# E-Reader.net
KiCad netlist of a schematic drawn in EAGLE
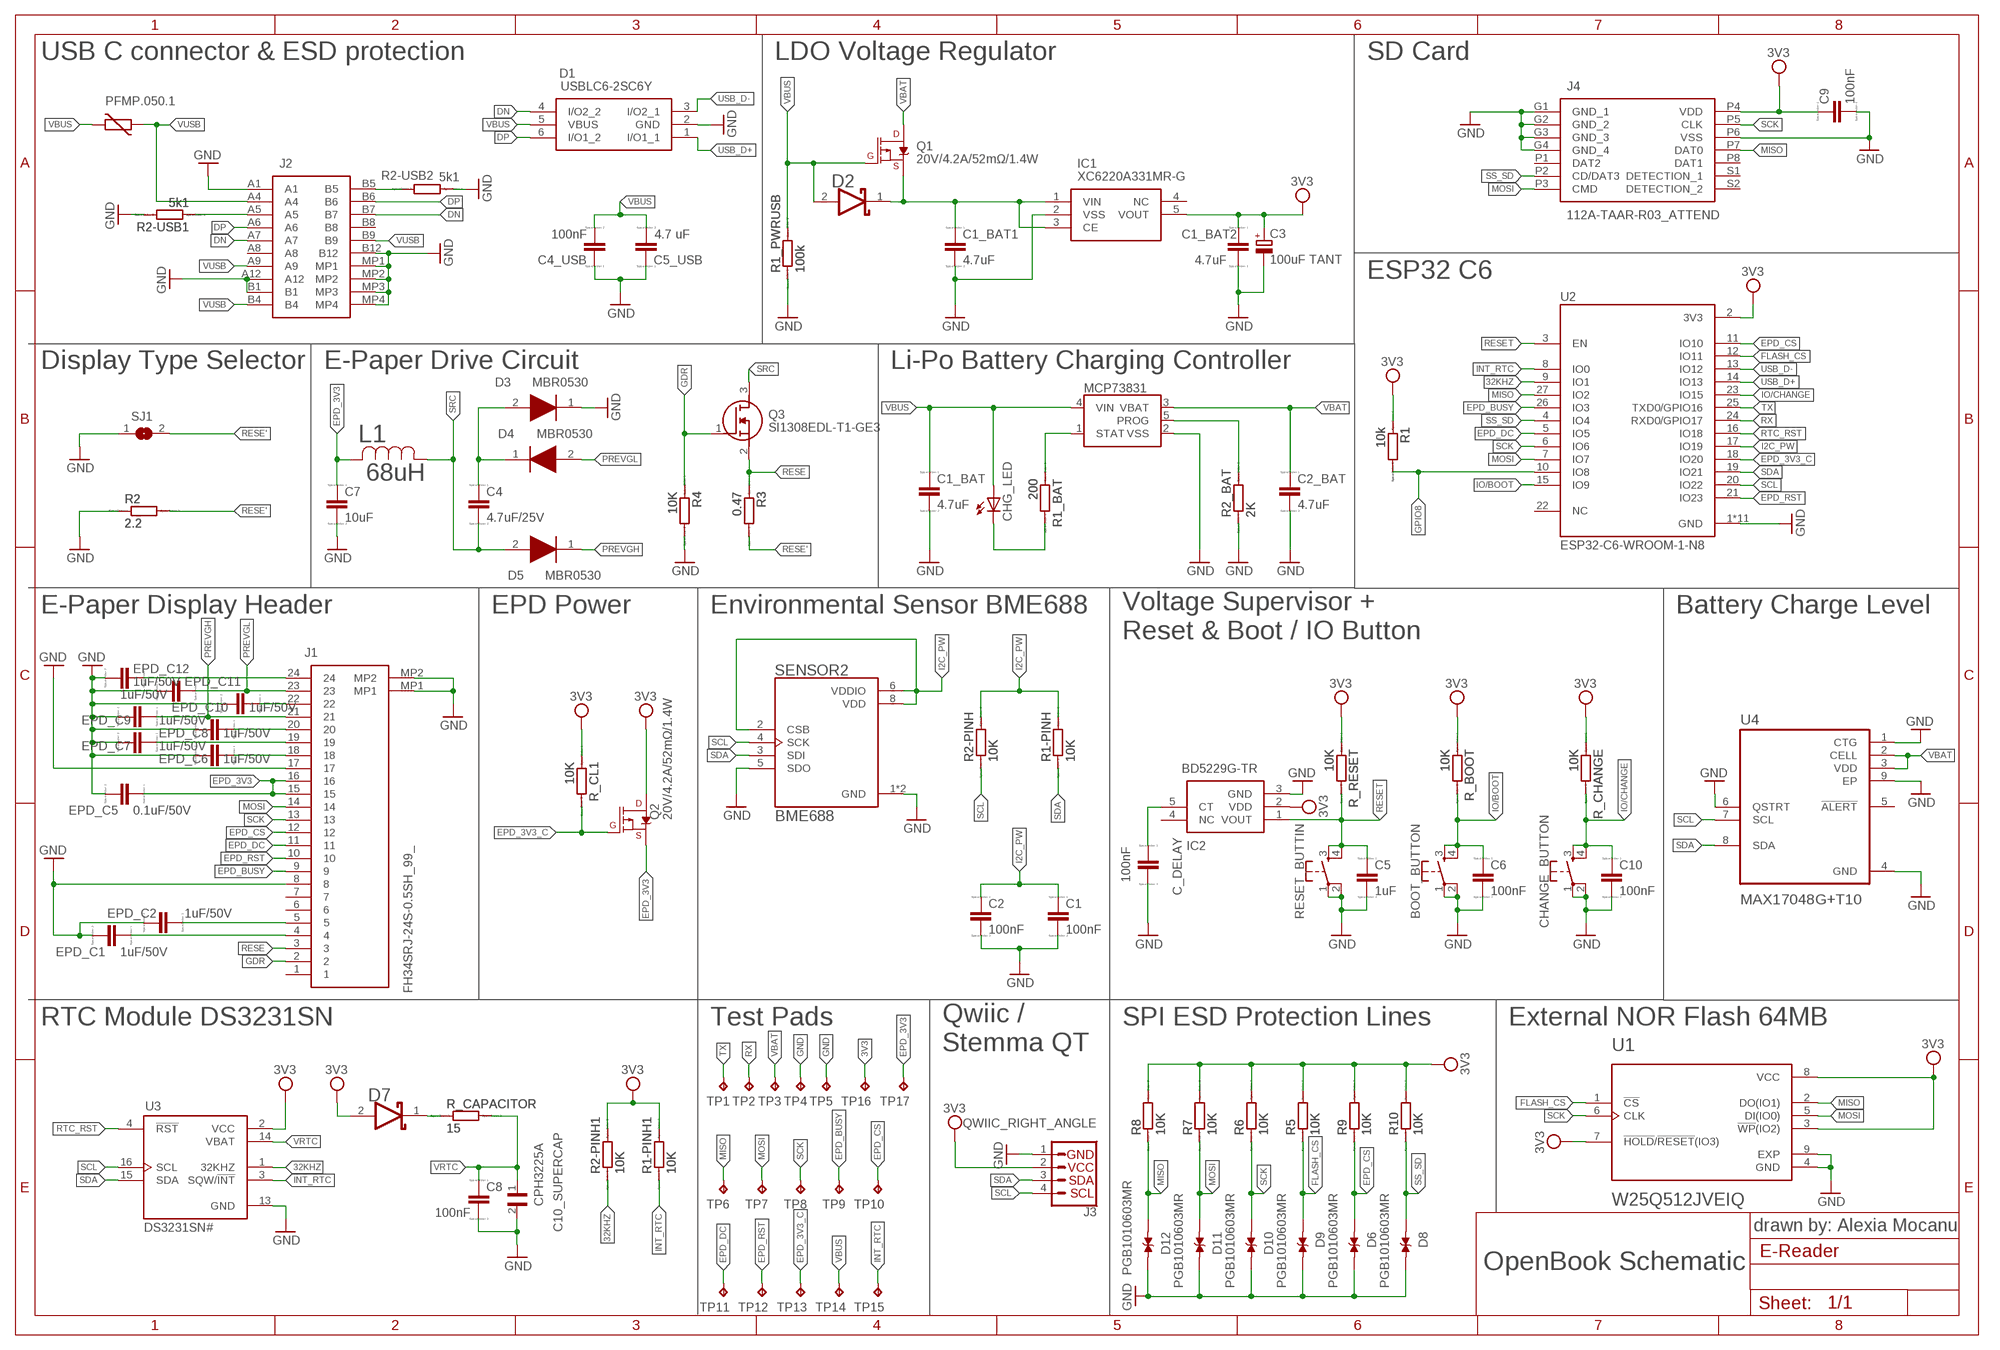
[diagram p0: schematic, sheet 1]

(export (version "E")
  (design (tool "Eeschema 10.0.6"))
  (components
    (comp (ref "BOOT_BUTTON")
      (value "BUTTON_CUSYOMV1")
      (footprint "eagle-import:MYBUTTON")
      (libsource (lib "eagle-import") (part "BUTTON_CUSYOMV1"))
    )
    (comp (ref "C1")
      (value "100nF")
      (footprint "eagle-import:EAGLE-LTSPICE_C0402")
      (libsource (lib "eagle-import") (part "EAGLE-LTSPICE_CC0402"))
    )
    (comp (ref "C1_BAT")
      (value "4.7uF")
      (footprint "eagle-import:EAGLE-LTSPICE_C0402")
      (libsource (lib "eagle-import") (part "EAGLE-LTSPICE_CC0402"))
    )
    (comp (ref "C1_BAT1")
      (value "4.7uF")
      (footprint "eagle-import:EAGLE-LTSPICE_C0402")
      (libsource (lib "eagle-import") (part "EAGLE-LTSPICE_CC0402"))
    )
    (comp (ref "C1_BAT2")
      (value "4.7uF")
      (footprint "eagle-import:EAGLE-LTSPICE_C0402")
      (libsource (lib "eagle-import") (part "EAGLE-LTSPICE_CC0402"))
    )
    (comp (ref "C2")
      (value "100nF")
      (footprint "eagle-import:EAGLE-LTSPICE_C0402")
      (libsource (lib "eagle-import") (part "EAGLE-LTSPICE_CC0402"))
    )
    (comp (ref "C2_BAT")
      (value "4.7uF")
      (footprint "eagle-import:EAGLE-LTSPICE_C0402")
      (libsource (lib "eagle-import") (part "EAGLE-LTSPICE_CC0402"))
    )
    (comp (ref "C3")
      (value "100uF TANT")
      (footprint "eagle-import:RCL_CT3528")
      (libsource (lib "eagle-import") (part "RCL_CPOL-EUCT3528"))
    )
    (comp (ref "C4")
      (value "4.7uF/25V")
      (footprint "eagle-import:EAGLE-LTSPICE_C0402")
      (libsource (lib "eagle-import") (part "EAGLE-LTSPICE_CC0402"))
    )
    (comp (ref "C4_USB")
      (value "100nF")
      (footprint "eagle-import:EAGLE-LTSPICE_C0402")
      (libsource (lib "eagle-import") (part "EAGLE-LTSPICE_CC0402"))
    )
    (comp (ref "C5")
      (value "1uF")
      (footprint "eagle-import:EAGLE-LTSPICE_C0402")
      (libsource (lib "eagle-import") (part "EAGLE-LTSPICE_CC0402"))
    )
    (comp (ref "C5_USB")
      (value "4.7 uF")
      (footprint "eagle-import:EAGLE-LTSPICE_C0402")
      (libsource (lib "eagle-import") (part "EAGLE-LTSPICE_CC0402"))
    )
    (comp (ref "C6")
      (value "100nF")
      (footprint "eagle-import:EAGLE-LTSPICE_C0402")
      (libsource (lib "eagle-import") (part "EAGLE-LTSPICE_CC0402"))
    )
    (comp (ref "C7")
      (value "10uF")
      (footprint "eagle-import:EAGLE-LTSPICE_C0402")
      (libsource (lib "eagle-import") (part "EAGLE-LTSPICE_CC0402"))
    )
    (comp (ref "C8")
      (value "100nF")
      (footprint "eagle-import:EAGLE-LTSPICE_C0402")
      (libsource (lib "eagle-import") (part "EAGLE-LTSPICE_CC0402"))
    )
    (comp (ref "C9")
      (value "100nF")
      (footprint "eagle-import:EAGLE-LTSPICE_C0402")
      (libsource (lib "eagle-import") (part "EAGLE-LTSPICE_CC0402"))
    )
    (comp (ref "C10")
      (value "100nF")
      (footprint "eagle-import:EAGLE-LTSPICE_C0402")
      (libsource (lib "eagle-import") (part "EAGLE-LTSPICE_CC0402"))
    )
    (comp (ref "C10_SUPERCAP")
      (value "CPH3225A")
      (footprint "eagle-import:CAPCP3225X100N")
      (fields (field (name "MF") "Seiko Instruments"))
      (libsource (lib "eagle-import") (part "CPH3225A"))
    )
    (comp (ref "CHANGE_BUTTON")
      (value "BUTTON_CUSYOMV1")
      (footprint "eagle-import:MYBUTTON")
      (libsource (lib "eagle-import") (part "BUTTON_CUSYOMV1"))
    )
    (comp (ref "CHG_LED")
      (value "ADAFRUIT_LEDCHIP-LED0603")
      (footprint "eagle-import:ADAFRUIT_CHIP-LED0603")
      (libsource (lib "eagle-import") (part "ADAFRUIT_LEDCHIP-LED0603"))
    )
    (comp (ref "C_DELAY")
      (value "100nF")
      (footprint "eagle-import:EAGLE-LTSPICE_C0402")
      (libsource (lib "eagle-import") (part "EAGLE-LTSPICE_CC0402"))
    )
    (comp (ref "D1")
      (value "USBLC6-2SC6Y")
      (footprint "eagle-import:SOT95P280X145-6N")
      (fields (field (name "MF") "STMicroelectronics"))
      (libsource (lib "eagle-import") (part "USBLC6-2SC6Y"))
    )
    (comp (ref "D2")
      (value "ESP32_WROVER_AVX---SD0805S020S1R0_AVX_SD0805S020S1R0_0_0AVX_SD0805S020S1R0_0_0")
      (footprint "eagle-import:ESP32_WROVER_AVX---SD0805S020S1R0_AVX_SD0805S020S1R0_0")
      (fields
        (field (name "DIGIKEY_PART_NUMBER") "478-7800-1-ND")
        (field (name "MF") "AVX")
        (field (name "MOUSER_PART_NUMBER") "581-SD0805S020S1R0")
      )
      (libsource (lib "eagle-import") (part "ESP32_WROVER_AVX---SD0805S020S1R0_AVX_SD0805S020S1R0_0_0AVX_SD0805S020S1R0_0_0"))
    )
    (comp (ref "D3")
      (value "MBR0530")
      (footprint "eagle-import:SOD3716X135N")
      (fields (field (name "MF") "ON Semiconductor"))
      (libsource (lib "eagle-import") (part "MBR0530"))
    )
    (comp (ref "D4")
      (value "MBR0530")
      (footprint "eagle-import:SOD3716X135N")
      (fields (field (name "MF") "ON Semiconductor"))
      (libsource (lib "eagle-import") (part "MBR0530"))
    )
    (comp (ref "D5")
      (value "MBR0530")
      (footprint "eagle-import:SOD3716X135N")
      (fields (field (name "MF") "ON Semiconductor"))
      (libsource (lib "eagle-import") (part "MBR0530"))
    )
    (comp (ref "D6")
      (value "PGB1010603MR")
      (footprint "eagle-import:DIOC1608X36N")
      (fields (field (name "MF") "Littelfuse Inc."))
      (libsource (lib "eagle-import") (part "PGB1010603MR"))
    )
    (comp (ref "D7")
      (value "SD0805S020S1R0")
      (footprint "eagle-import:ESP32_WROVER_AVX---SD0805S020S1R0_AVX_SD0805S020S1R0_0")
      (fields
        (field (name "DIGIKEY_PART_NUMBER") "478-7800-1-ND")
        (field (name "MF") "AVX")
        (field (name "MOUSER_PART_NUMBER") "581-SD0805S020S1R0")
      )
      (libsource (lib "eagle-import") (part "ESP32_WROVER_AVX---SD0805S020S1R0_AVX_SD0805S020S1R0_0_0AVX_SD0805S020S1R0_0_0"))
    )
    (comp (ref "D8")
      (value "PGB1010603MR")
      (footprint "eagle-import:DIOC1608X36N")
      (fields (field (name "MF") "Littelfuse Inc."))
      (libsource (lib "eagle-import") (part "PGB1010603MR"))
    )
    (comp (ref "D9")
      (value "PGB1010603MR")
      (footprint "eagle-import:DIOC1608X36N")
      (fields (field (name "MF") "Littelfuse Inc."))
      (libsource (lib "eagle-import") (part "PGB1010603MR"))
    )
    (comp (ref "D10")
      (value "PGB1010603MR")
      (footprint "eagle-import:DIOC1608X36N")
      (fields (field (name "MF") "Littelfuse Inc."))
      (libsource (lib "eagle-import") (part "PGB1010603MR"))
    )
    (comp (ref "D11")
      (value "PGB1010603MR")
      (footprint "eagle-import:DIOC1608X36N")
      (fields (field (name "MF") "Littelfuse Inc."))
      (libsource (lib "eagle-import") (part "PGB1010603MR"))
    )
    (comp (ref "D12")
      (value "PGB1010603MR")
      (footprint "eagle-import:DIOC1608X36N")
      (fields (field (name "MF") "Littelfuse Inc."))
      (libsource (lib "eagle-import") (part "PGB1010603MR"))
    )
    (comp (ref "EPD_C1")
      (value "1uF/50V")
      (footprint "eagle-import:EAGLE-LTSPICE_C0402")
      (libsource (lib "eagle-import") (part "EAGLE-LTSPICE_CC0402"))
    )
    (comp (ref "EPD_C2")
      (value "1uF/50V")
      (footprint "eagle-import:EAGLE-LTSPICE_C0402")
      (libsource (lib "eagle-import") (part "EAGLE-LTSPICE_CC0402"))
    )
    (comp (ref "EPD_C5")
      (value "0.1uF/50V")
      (footprint "eagle-import:EAGLE-LTSPICE_C0402")
      (libsource (lib "eagle-import") (part "EAGLE-LTSPICE_CC0402"))
    )
    (comp (ref "EPD_C6")
      (value "1uF/50V")
      (footprint "eagle-import:EAGLE-LTSPICE_C0402")
      (libsource (lib "eagle-import") (part "EAGLE-LTSPICE_CC0402"))
    )
    (comp (ref "EPD_C7")
      (value "1uF/50V")
      (footprint "eagle-import:EAGLE-LTSPICE_C0402")
      (libsource (lib "eagle-import") (part "EAGLE-LTSPICE_CC0402"))
    )
    (comp (ref "EPD_C8")
      (value "1uF/50V")
      (footprint "eagle-import:EAGLE-LTSPICE_C0402")
      (libsource (lib "eagle-import") (part "EAGLE-LTSPICE_CC0402"))
    )
    (comp (ref "EPD_C9")
      (value "1uF/50V")
      (footprint "eagle-import:EAGLE-LTSPICE_C0402")
      (libsource (lib "eagle-import") (part "EAGLE-LTSPICE_CC0402"))
    )
    (comp (ref "EPD_C10")
      (value "1uF/50V")
      (footprint "eagle-import:EAGLE-LTSPICE_C0402")
      (libsource (lib "eagle-import") (part "EAGLE-LTSPICE_CC0402"))
    )
    (comp (ref "EPD_C11")
      (value "1uF/50V")
      (footprint "eagle-import:EAGLE-LTSPICE_C0402")
      (libsource (lib "eagle-import") (part "EAGLE-LTSPICE_CC0402"))
    )
    (comp (ref "EPD_C12")
      (value "1uF/50V")
      (footprint "eagle-import:EAGLE-LTSPICE_C0402")
      (libsource (lib "eagle-import") (part "EAGLE-LTSPICE_CC0402"))
    )
    (comp (ref "IC1")
      (value "XC6220A331MR-G")
      (footprint "eagle-import:SOT95P280X120-5N")
      (fields (field (name "MOUSER_PART_NUMBER") "865-XC6220A331MR-G"))
      (libsource (lib "eagle-import") (part "XC6220A331MR-G"))
    )
    (comp (ref "IC2")
      (value "BD5229G-TR")
      (footprint "eagle-import:SOT95P280X125-5N")
      (fields (field (name "MOUSER_PART_NUMBER") "755-BD5229G-TR"))
      (libsource (lib "eagle-import") (part "BD5229G-TR"))
    )
    (comp (ref "J1")
      (value "FH34SRJ-24S-0.5SH_99_")
      (footprint "eagle-import:FH34SRJ24S05SH99")
      (fields
        (field (name "MANUFACTURER_PART_NUMBER") "FH34SRJ-24S-0.5SH(99)")
        (field (name "MOUSER_PART_NUMBER") "798-FH34SRJ24S05SH99")
      )
      (libsource (lib "eagle-import") (part "FH34SRJ-24S-0.5SH_99_"))
    )
    (comp (ref "J2")
      (value "SAMACSYS_PARTS_USB4110-GF-A")
      (footprint "eagle-import:SAMACSYS_PARTS_USB4110GFA")
      (fields
        (field (name "MANUFACTURER_PART_NUMBER") "USB4110-GF-A")
        (field (name "MOUSER_PART_NUMBER") "640-USB4110-GF-A")
      )
      (libsource (lib "eagle-import") (part "SAMACSYS_PARTS_USB4110-GF-A"))
    )
    (comp (ref "J3")
      (value "QWIIC_RIGHT_ANGLE")
      (footprint "eagle-import:JST04_1MM_RA")
      (libsource (lib "eagle-import") (part "QWIIC_CONNECTORJS-1MM"))
    )
    (comp (ref "J4")
      (value "112A-TAAR-R03_ATTEND")
      (footprint "eagle-import:112ATAARR03ATTEND")
      (fields (field (name "MANUFACTURER_PART_NUMBER") "112A-TAAR-R03 ATTEND"))
      (libsource (lib "eagle-import") (part "112A-TAAR-R03_ATTEND"))
    )
    (comp (ref "L1")
      (value "68uH")
      (footprint "eagle-import:IND_4828-WE-TPC_WRE")
      (fields
        (field (name "MANUFACTURER_PART_NUMBER") "744043680")
        (field (name "COPYRIGHT") "Copyright (C) 2024 Ultra Librarian. All rights reserved.")
      )
      (libsource (lib "eagle-import") (part "744043680IND_4828-WE-TPC_WRE"))
    )
    (comp (ref "MCP73831")
      (value "ESP32_WROVER_SPARKFUN-IC-POWER_MCP73831")
      (footprint "eagle-import:ESP32_WROVER_SPARKFUN-IC-POWER_SOT23-5")
      (libsource (lib "eagle-import") (part "ESP32_WROVER_SPARKFUN-IC-POWER_MCP73831"))
    )
    (comp (ref "PFMP.050.1")
      (value "ESP32C6_VARISTORCN1812")
      (footprint "eagle-import:ESP32C6_VARISTOR_CT_CN1812")
      (libsource (lib "eagle-import") (part "ESP32C6_VARISTORCN1812"))
    )
    (comp (ref "Q1")
      (value "20V/4.2A/52mΩ/1.4W")
      (footprint "eagle-import:ESP32_WROVER_SPARKFUN-DISCRETESEMI_SOT23-3")
      (libsource (lib "eagle-import") (part "ESP32_WROVER_SPARKFUN-DISCRETESEMI_MOSFET_PCH-DMG2305UX-7"))
    )
    (comp (ref "Q2")
      (value "20V/4.2A/52mΩ/1.4W")
      (footprint "eagle-import:ESP32_WROVER_SPARKFUN-DISCRETESEMI_SOT23-3")
      (fields (field (name "SPICEPREFIX") "Q"))
      (libsource (lib "eagle-import") (part "ESP32_WROVER_SPARKFUN-DISCRETESEMI_MOSFET_PCH-DMG2305UX-7"))
    )
    (comp (ref "Q3")
      (value "SI1308EDL-T1-GE3")
      (footprint "eagle-import:SOT65P210X110-3N")
      (fields (field (name "MF") "Vishay Siliconix"))
      (libsource (lib "eagle-import") (part "SI1308EDL-T1-GE3"))
    )
    (comp (ref "R1")
      (value "10k")
      (footprint "eagle-import:ESP32_WROVER_EAGLE-LTSPICE_R0402")
      (libsource (lib "eagle-import") (part "ESP32_WROVER_EAGLE-LTSPICE_RR0402"))
    )
    (comp (ref "R1-PINH")
      (value "10K")
      (footprint "eagle-import:ESP32_WROVER_EAGLE-LTSPICE_R0402")
      (libsource (lib "eagle-import") (part "ESP32_WROVER_EAGLE-LTSPICE_RR0402"))
    )
    (comp (ref "R1-PINH1")
      (value "10K")
      (footprint "eagle-import:ESP32_WROVER_EAGLE-LTSPICE_R0402")
      (libsource (lib "eagle-import") (part "ESP32_WROVER_EAGLE-LTSPICE_RR0402"))
    )
    (comp (ref "R1_BAT")
      (value "200")
      (footprint "eagle-import:ESP32_WROVER_EAGLE-LTSPICE_R0402")
      (libsource (lib "eagle-import") (part "ESP32_WROVER_EAGLE-LTSPICE_RR0402"))
    )
    (comp (ref "R1_PWRUSB")
      (value "100k")
      (footprint "eagle-import:ESP32_WROVER_EAGLE-LTSPICE_R0402")
      (libsource (lib "eagle-import") (part "ESP32_WROVER_EAGLE-LTSPICE_RR0402"))
    )
    (comp (ref "R2")
      (value "2.2")
      (footprint "eagle-import:ESP32_WROVER_EAGLE-LTSPICE_R0402")
      (libsource (lib "eagle-import") (part "ESP32_WROVER_EAGLE-LTSPICE_RR0402"))
    )
    (comp (ref "R2-PINH")
      (value "10K")
      (footprint "eagle-import:ESP32_WROVER_EAGLE-LTSPICE_R0402")
      (libsource (lib "eagle-import") (part "ESP32_WROVER_EAGLE-LTSPICE_RR0402"))
    )
    (comp (ref "R2-PINH1")
      (value "10K")
      (footprint "eagle-import:ESP32_WROVER_EAGLE-LTSPICE_R0402")
      (libsource (lib "eagle-import") (part "ESP32_WROVER_EAGLE-LTSPICE_RR0402"))
    )
    (comp (ref "R2-USB1")
      (value "5k1")
      (footprint "eagle-import:ESP32_WROVER_EAGLE-LTSPICE_R0402")
      (libsource (lib "eagle-import") (part "ESP32_WROVER_EAGLE-LTSPICE_RR0402"))
    )
    (comp (ref "R2-USB2")
      (value "5k1")
      (footprint "eagle-import:ESP32_WROVER_EAGLE-LTSPICE_R0402")
      (libsource (lib "eagle-import") (part "ESP32_WROVER_EAGLE-LTSPICE_RR0402"))
    )
    (comp (ref "R2_BAT")
      (value "2K")
      (footprint "eagle-import:ESP32_WROVER_EAGLE-LTSPICE_R0402")
      (libsource (lib "eagle-import") (part "ESP32_WROVER_EAGLE-LTSPICE_RR0402"))
    )
    (comp (ref "R3")
      (value "0.47")
      (footprint "eagle-import:ESP32_WROVER_EAGLE-LTSPICE_R0402")
      (libsource (lib "eagle-import") (part "ESP32_WROVER_EAGLE-LTSPICE_RR0402"))
    )
    (comp (ref "R4")
      (value "10K")
      (footprint "eagle-import:ESP32_WROVER_EAGLE-LTSPICE_R0402")
      (libsource (lib "eagle-import") (part "ESP32_WROVER_EAGLE-LTSPICE_RR0402"))
    )
    (comp (ref "R5")
      (value "10K")
      (footprint "eagle-import:ESP32_WROVER_EAGLE-LTSPICE_R0402")
      (libsource (lib "eagle-import") (part "ESP32_WROVER_EAGLE-LTSPICE_RR0402"))
    )
    (comp (ref "R6")
      (value "10K")
      (footprint "eagle-import:ESP32_WROVER_EAGLE-LTSPICE_R0402")
      (libsource (lib "eagle-import") (part "ESP32_WROVER_EAGLE-LTSPICE_RR0402"))
    )
    (comp (ref "R7")
      (value "10K")
      (footprint "eagle-import:ESP32_WROVER_EAGLE-LTSPICE_R0402")
      (libsource (lib "eagle-import") (part "ESP32_WROVER_EAGLE-LTSPICE_RR0402"))
    )
    (comp (ref "R8")
      (value "10K")
      (footprint "eagle-import:ESP32_WROVER_EAGLE-LTSPICE_R0402")
      (libsource (lib "eagle-import") (part "ESP32_WROVER_EAGLE-LTSPICE_RR0402"))
    )
    (comp (ref "R9")
      (value "10K")
      (footprint "eagle-import:ESP32_WROVER_EAGLE-LTSPICE_R0402")
      (libsource (lib "eagle-import") (part "ESP32_WROVER_EAGLE-LTSPICE_RR0402"))
    )
    (comp (ref "R10")
      (value "10K")
      (footprint "eagle-import:ESP32_WROVER_EAGLE-LTSPICE_R0402")
      (libsource (lib "eagle-import") (part "ESP32_WROVER_EAGLE-LTSPICE_RR0402"))
    )
    (comp (ref "RESET_BUTTIN")
      (value "BUTTON_CUSYOMV1")
      (footprint "eagle-import:MYBUTTON")
      (libsource (lib "eagle-import") (part "BUTTON_CUSYOMV1"))
    )
    (comp (ref "R_BOOT")
      (value "10K")
      (footprint "eagle-import:ESP32_WROVER_EAGLE-LTSPICE_R0402")
      (libsource (lib "eagle-import") (part "ESP32_WROVER_EAGLE-LTSPICE_RR0402"))
    )
    (comp (ref "R_CAPACITOR")
      (value "15")
      (footprint "eagle-import:ESP32_WROVER_EAGLE-LTSPICE_R0402")
      (libsource (lib "eagle-import") (part "ESP32_WROVER_EAGLE-LTSPICE_RR0402"))
    )
    (comp (ref "R_CHANGE")
      (value "10K")
      (footprint "eagle-import:ESP32_WROVER_EAGLE-LTSPICE_R0402")
      (libsource (lib "eagle-import") (part "ESP32_WROVER_EAGLE-LTSPICE_RR0402"))
    )
    (comp (ref "R_CL1")
      (value "10K")
      (footprint "eagle-import:ESP32_WROVER_EAGLE-LTSPICE_R0402")
      (libsource (lib "eagle-import") (part "ESP32_WROVER_EAGLE-LTSPICE_RR0402"))
    )
    (comp (ref "R_RESET")
      (value "10K")
      (footprint "eagle-import:ESP32_WROVER_EAGLE-LTSPICE_R0402")
      (libsource (lib "eagle-import") (part "ESP32_WROVER_EAGLE-LTSPICE_RR0402"))
    )
    (comp (ref "SENSOR2")
      (value "BME688")
      (footprint "eagle-import:ESP32_WROVER_BME680_PSON80P300X300X100-8N")
      (fields (field (name "MF") "Bosch Sensortec") (field (name "MP") "BME680"))
      (libsource (lib "eagle-import") (part "ESP32_WROVER_BME680_BME680"))
    )
    (comp (ref "SJ1") (value "SJ") (footprint "eagle-import:SJ") (libsource (lib "eagle-import") (part "SJ")))
    (comp (ref "TP1")
      (value "TPTP20R")
      (footprint "eagle-import:TP20R")
      (libsource (lib "eagle-import") (part "TPTP20R"))
    )
    (comp (ref "TP2")
      (value "TPTP20R")
      (footprint "eagle-import:TP20R")
      (libsource (lib "eagle-import") (part "TPTP20R"))
    )
    (comp (ref "TP3")
      (value "TPTP20R")
      (footprint "eagle-import:TP20R")
      (libsource (lib "eagle-import") (part "TPTP20R"))
    )
    (comp (ref "TP4")
      (value "TPTP20R")
      (footprint "eagle-import:TP20R")
      (libsource (lib "eagle-import") (part "TPTP20R"))
    )
    (comp (ref "TP5")
      (value "TPTP20R")
      (footprint "eagle-import:TP20R")
      (libsource (lib "eagle-import") (part "TPTP20R"))
    )
    (comp (ref "TP6")
      (value "TPTP20R")
      (footprint "eagle-import:TP20R")
      (libsource (lib "eagle-import") (part "TPTP20R"))
    )
    (comp (ref "TP7")
      (value "TPTP20R")
      (footprint "eagle-import:TP20R")
      (libsource (lib "eagle-import") (part "TPTP20R"))
    )
    (comp (ref "TP8")
      (value "TPTP20R")
      (footprint "eagle-import:TP20R")
      (libsource (lib "eagle-import") (part "TPTP20R"))
    )
    (comp (ref "TP9")
      (value "TPTP20R")
      (footprint "eagle-import:TP20R")
      (libsource (lib "eagle-import") (part "TPTP20R"))
    )
    (comp (ref "TP10")
      (value "TPTP20R")
      (footprint "eagle-import:TP20R")
      (libsource (lib "eagle-import") (part "TPTP20R"))
    )
    (comp (ref "TP11")
      (value "TPTP20R")
      (footprint "eagle-import:TP20R")
      (libsource (lib "eagle-import") (part "TPTP20R"))
    )
    (comp (ref "TP12")
      (value "TPTP20R")
      (footprint "eagle-import:TP20R")
      (libsource (lib "eagle-import") (part "TPTP20R"))
    )
    (comp (ref "TP13")
      (value "TPTP20R")
      (footprint "eagle-import:TP20R")
      (libsource (lib "eagle-import") (part "TPTP20R"))
    )
    (comp (ref "TP14")
      (value "TPTP20R")
      (footprint "eagle-import:TP20R")
      (libsource (lib "eagle-import") (part "TPTP20R"))
    )
    (comp (ref "TP15")
      (value "TPTP20R")
      (footprint "eagle-import:TP20R")
      (libsource (lib "eagle-import") (part "TPTP20R"))
    )
    (comp (ref "TP16")
      (value "TPTP20R")
      (footprint "eagle-import:TP20R")
      (libsource (lib "eagle-import") (part "TPTP20R"))
    )
    (comp (ref "TP17")
      (value "TPTP20R")
      (footprint "eagle-import:TP20R")
      (libsource (lib "eagle-import") (part "TPTP20R"))
    )
    (comp (ref "U1")
      (value "W25Q512JVEIQ")
      (footprint "eagle-import:SON127P600X800X80-9N")
      (fields (field (name "MF") "Winbond Electronics"))
      (libsource (lib "eagle-import") (part "W25Q512JVEIQ"))
    )
    (comp (ref "U2")
      (value "ESP32-C6-WROOM-1-N8")
      (footprint "eagle-import:XCVR_ESP32-C6-WROOM-1-N8")
      (fields (field (name "MF") "Espressif Systems"))
      (libsource (lib "eagle-import") (part "ESP32-C6-WROOM-1-N8"))
    )
    (comp (ref "U3")
      (value "DS3231SN#")
      (footprint "eagle-import:SOIC127P1032X265-16N")
      (fields (field (name "MF") "Analog Devices"))
      (libsource (lib "eagle-import") (part "DS3231SN#"))
    )
    (comp (ref "U4")
      (value "MAX17048G+T10")
      (footprint "eagle-import:SON50P200X200X80-9N")
      (fields (field (name "MF") "Analog Devices"))
      (libsource (lib "eagle-import") (part "MAX17048G+T10"))
    )
  )
  (nets
    (net (code "1") (name "3V3") (class "Default")
      (node (ref "C1_BAT2") (pin "1") (pinfunction "1_1") (pintype "passive"))
      (node (ref "C3") (pin "+") (pinfunction "+_+") (pintype "passive"))
      (node (ref "C9") (pin "1") (pinfunction "1_1") (pintype "passive"))
      (node (ref "D7") (pin "2") (pinfunction "ANODE_2") (pintype "bidirectional"))
      (node (ref "IC1") (pin "5") (pinfunction "VOUT_5") (pintype "bidirectional"))
      (node (ref "IC2") (pin "2") (pinfunction "VDD_2") (pintype "bidirectional"))
      (node (ref "J3") (pin "2") (pinfunction "2_2") (pintype "power_in"))
      (node (ref "J4") (pin "P4") (pinfunction "VDD_P4") (pintype "bidirectional"))
      (node (ref "Q2") (pin "3") (pinfunction "D_3") (pintype "bidirectional"))
      (node (ref "R1") (pin "1") (pinfunction "1_1") (pintype "passive"))
      (node (ref "R1-PINH1") (pin "2") (pinfunction "2_2") (pintype "passive"))
      (node (ref "R10") (pin "2") (pinfunction "2_2") (pintype "passive"))
      (node (ref "R2-PINH1") (pin "2") (pinfunction "2_2") (pintype "passive"))
      (node (ref "R5") (pin "2") (pinfunction "2_2") (pintype "passive"))
      (node (ref "R6") (pin "2") (pinfunction "2_2") (pintype "passive"))
      (node (ref "R7") (pin "2") (pinfunction "2_2") (pintype "passive"))
      (node (ref "R8") (pin "2") (pinfunction "2_2") (pintype "passive"))
      (node (ref "R9") (pin "2") (pinfunction "2_2") (pintype "passive"))
      (node (ref "R_BOOT") (pin "1") (pinfunction "1_1") (pintype "passive"))
      (node (ref "R_CHANGE") (pin "1") (pinfunction "1_1") (pintype "passive"))
      (node (ref "R_CL1") (pin "1") (pinfunction "1_1") (pintype "passive"))
      (node (ref "R_RESET") (pin "1") (pinfunction "1_1") (pintype "passive"))
      (node (ref "TP16") (pin "TP") (pinfunction "TP_TP") (pintype "input"))
      (node (ref "U1") (pin "3") (pinfunction "~{WP}(IO2)_3") (pintype "bidirectional"))
      (node (ref "U1") (pin "7") (pinfunction "~{HOLD}/~{RESET}(IO3)_7") (pintype "bidirectional"))
      (node (ref "U1") (pin "8") (pinfunction "VCC_8") (pintype "power_in"))
      (node (ref "U2") (pin "2") (pinfunction "3V3_2") (pintype "power_in"))
      (node (ref "U3") (pin "2") (pinfunction "VCC_2") (pintype "power_in"))
    )
    (net (code "2") (name "32KHZ") (class "Default")
      (node (ref "R2-PINH1") (pin "1") (pinfunction "1_1") (pintype "passive"))
      (node (ref "U2") (pin "9") (pinfunction "IO1_9") (pintype "bidirectional"))
      (node (ref "U3") (pin "1") (pinfunction "32KHZ_1") (pintype "output"))
    )
    (net (code "3") (name "DN") (class "Default")
      (node (ref "D1") (pin "4") (pinfunction "I/O2_2_4") (pintype "bidirectional"))
      (node (ref "J2") (pin "A7") (pinfunction "A7_A7") (pintype "bidirectional"))
      (node (ref "J2") (pin "B7") (pinfunction "B7_B7") (pintype "bidirectional"))
    )
    (net (code "4") (name "DP") (class "Default")
      (node (ref "D1") (pin "6") (pinfunction "I/O1_2_6") (pintype "bidirectional"))
      (node (ref "J2") (pin "A6") (pinfunction "A6_A6") (pintype "bidirectional"))
      (node (ref "J2") (pin "B6") (pinfunction "B6_B6") (pintype "bidirectional"))
    )
    (net (code "5") (name "EPD_3V3") (class "Default")
      (node (ref "C7") (pin "1") (pinfunction "1_1") (pintype "passive"))
      (node (ref "EPD_C5") (pin "1") (pinfunction "1_1") (pintype "passive"))
      (node (ref "J1") (pin "15") (pinfunction "15_15") (pintype "bidirectional"))
      (node (ref "J1") (pin "16") (pinfunction "16_16") (pintype "bidirectional"))
      (node (ref "L1") (pin "2") (pinfunction "2_2") (pintype "passive"))
      (node (ref "Q2") (pin "2") (pinfunction "S_2") (pintype "bidirectional"))
      (node (ref "TP17") (pin "TP") (pinfunction "TP_TP") (pintype "input"))
    )
    (net (code "6") (name "EPD_3V3_C") (class "Default")
      (node (ref "Q2") (pin "1") (pinfunction "G_1") (pintype "bidirectional"))
      (node (ref "R_CL1") (pin "2") (pinfunction "2_2") (pintype "passive"))
      (node (ref "TP13") (pin "TP") (pinfunction "TP_TP") (pintype "input"))
      (node (ref "U2") (pin "18") (pinfunction "IO20_18") (pintype "bidirectional"))
    )
    (net (code "7") (name "EPD_BUSY") (class "Default")
      (node (ref "J1") (pin "9") (pinfunction "9_9") (pintype "bidirectional"))
      (node (ref "TP9") (pin "TP") (pinfunction "TP_TP") (pintype "input"))
      (node (ref "U2") (pin "26") (pinfunction "IO3_26") (pintype "bidirectional"))
    )
    (net (code "8") (name "EPD_CS") (class "Default")
      (node (ref "D6") (pin "1") (pinfunction "1_1") (pintype "passive"))
      (node (ref "J1") (pin "12") (pinfunction "12_12") (pintype "bidirectional"))
      (node (ref "R9") (pin "1") (pinfunction "1_1") (pintype "passive"))
      (node (ref "TP10") (pin "TP") (pinfunction "TP_TP") (pintype "input"))
      (node (ref "U2") (pin "11") (pinfunction "IO10_11") (pintype "bidirectional"))
    )
    (net (code "9") (name "EPD_DC") (class "Default")
      (node (ref "J1") (pin "11") (pinfunction "11_11") (pintype "bidirectional"))
      (node (ref "TP11") (pin "TP") (pinfunction "TP_TP") (pintype "input"))
      (node (ref "U2") (pin "5") (pinfunction "IO5_5") (pintype "bidirectional"))
    )
    (net (code "10") (name "EPD_RST") (class "Default")
      (node (ref "J1") (pin "10") (pinfunction "10_10") (pintype "bidirectional"))
      (node (ref "TP12") (pin "TP") (pinfunction "TP_TP") (pintype "input"))
      (node (ref "U2") (pin "21") (pinfunction "IO23_21") (pintype "bidirectional"))
    )
    (net (code "11") (name "FLASH_CS") (class "Default")
      (node (ref "D9") (pin "1") (pinfunction "1_1") (pintype "passive"))
      (node (ref "R5") (pin "1") (pinfunction "1_1") (pintype "passive"))
      (node (ref "U1") (pin "1") (pinfunction "~{CS}_1") (pintype "input"))
      (node (ref "U2") (pin "12") (pinfunction "IO11_12") (pintype "bidirectional"))
    )
    (net (code "12") (name "GDR") (class "Default")
      (node (ref "J1") (pin "2") (pinfunction "2_2") (pintype "bidirectional"))
      (node (ref "Q3") (pin "1") (pinfunction "G_1") (pintype "bidirectional"))
      (node (ref "R4") (pin "1") (pinfunction "1_1") (pintype "passive"))
    )
    (net (code "13") (name "GND") (class "Default")
      (node (ref "BOOT_BUTTON") (pin "1") (pinfunction "1_1") (pintype "passive"))
      (node (ref "BOOT_BUTTON") (pin "2") (pinfunction "2_2") (pintype "passive"))
      (node (ref "C1") (pin "2") (pinfunction "2_2") (pintype "passive"))
      (node (ref "C10") (pin "2") (pinfunction "2_2") (pintype "passive"))
      (node (ref "C10_SUPERCAP") (pin "2") (pinfunction "2_2") (pintype "passive"))
      (node (ref "C1_BAT") (pin "2") (pinfunction "2_2") (pintype "passive"))
      (node (ref "C1_BAT1") (pin "2") (pinfunction "2_2") (pintype "passive"))
      (node (ref "C1_BAT2") (pin "2") (pinfunction "2_2") (pintype "passive"))
      (node (ref "C2") (pin "2") (pinfunction "2_2") (pintype "passive"))
      (node (ref "C2_BAT") (pin "2") (pinfunction "2_2") (pintype "passive"))
      (node (ref "C3") (pin "-") (pinfunction "-_-") (pintype "passive"))
      (node (ref "C4_USB") (pin "1") (pinfunction "1_1") (pintype "passive"))
      (node (ref "C5") (pin "2") (pinfunction "2_2") (pintype "passive"))
      (node (ref "C5_USB") (pin "1") (pinfunction "1_1") (pintype "passive"))
      (node (ref "C6") (pin "2") (pinfunction "2_2") (pintype "passive"))
      (node (ref "C7") (pin "2") (pinfunction "2_2") (pintype "passive"))
      (node (ref "C8") (pin "2") (pinfunction "2_2") (pintype "passive"))
      (node (ref "C9") (pin "2") (pinfunction "2_2") (pintype "passive"))
      (node (ref "CHANGE_BUTTON") (pin "1") (pinfunction "1_1") (pintype "passive"))
      (node (ref "CHANGE_BUTTON") (pin "2") (pinfunction "2_2") (pintype "passive"))
      (node (ref "C_DELAY") (pin "2") (pinfunction "2_2") (pintype "passive"))
      (node (ref "D1") (pin "2") (pinfunction "GND_2") (pintype "bidirectional"))
      (node (ref "D10") (pin "2") (pinfunction "2_2") (pintype "passive"))
      (node (ref "D11") (pin "2") (pinfunction "2_2") (pintype "passive"))
      (node (ref "D12") (pin "2") (pinfunction "2_2") (pintype "passive"))
      (node (ref "D3") (pin "1") (pinfunction "K_1") (pintype "bidirectional"))
      (node (ref "D6") (pin "2") (pinfunction "2_2") (pintype "passive"))
      (node (ref "D8") (pin "2") (pinfunction "2_2") (pintype "passive"))
      (node (ref "D9") (pin "2") (pinfunction "2_2") (pintype "passive"))
      (node (ref "EPD_C1") (pin "2") (pinfunction "2_2") (pintype "passive"))
      (node (ref "EPD_C10") (pin "2") (pinfunction "2_2") (pintype "passive"))
      (node (ref "EPD_C11") (pin "2") (pinfunction "2_2") (pintype "passive"))
      (node (ref "EPD_C12") (pin "2") (pinfunction "2_2") (pintype "passive"))
      (node (ref "EPD_C2") (pin "2") (pinfunction "2_2") (pintype "passive"))
      (node (ref "EPD_C5") (pin "2") (pinfunction "2_2") (pintype "passive"))
      (node (ref "EPD_C6") (pin "2") (pinfunction "2_2") (pintype "passive"))
      (node (ref "EPD_C7") (pin "2") (pinfunction "2_2") (pintype "passive"))
      (node (ref "EPD_C8") (pin "2") (pinfunction "2_2") (pintype "passive"))
      (node (ref "EPD_C9") (pin "2") (pinfunction "2_2") (pintype "passive"))
      (node (ref "IC1") (pin "2") (pinfunction "VSS_2") (pintype "bidirectional"))
      (node (ref "IC2") (pin "3") (pinfunction "GND_3") (pintype "bidirectional"))
      (node (ref "J1") (pin "17") (pinfunction "17_17") (pintype "bidirectional"))
      (node (ref "J1") (pin "8") (pinfunction "8_8") (pintype "bidirectional"))
      (node (ref "J1") (pin "MP1") (pinfunction "MP1_MP1") (pintype "bidirectional"))
      (node (ref "J1") (pin "MP2") (pinfunction "MP2_MP2") (pintype "bidirectional"))
      (node (ref "J2") (pin "A1") (pinfunction "A1_A1") (pintype "bidirectional"))
      (node (ref "J2") (pin "A12") (pinfunction "A12_A12") (pintype "bidirectional"))
      (node (ref "J2") (pin "B1") (pinfunction "B1_B1") (pintype "bidirectional"))
      (node (ref "J2") (pin "B12") (pinfunction "B12_B12") (pintype "bidirectional"))
      (node (ref "J2") (pin "MP1") (pinfunction "MP1_MP1") (pintype "bidirectional"))
      (node (ref "J2") (pin "MP2") (pinfunction "MP2_MP2") (pintype "bidirectional"))
      (node (ref "J2") (pin "MP3") (pinfunction "MP3_MP3") (pintype "bidirectional"))
      (node (ref "J2") (pin "MP4") (pinfunction "MP4_MP4") (pintype "bidirectional"))
      (node (ref "J3") (pin "1") (pinfunction "1_1") (pintype "power_in"))
      (node (ref "J4") (pin "G1") (pinfunction "GND_1_G1") (pintype "bidirectional"))
      (node (ref "J4") (pin "G2") (pinfunction "GND_2_G2") (pintype "bidirectional"))
      (node (ref "J4") (pin "G3") (pinfunction "GND_3_G3") (pintype "bidirectional"))
      (node (ref "J4") (pin "G4") (pinfunction "GND_4_G4") (pintype "bidirectional"))
      (node (ref "J4") (pin "P6") (pinfunction "VSS_P6") (pintype "bidirectional"))
      (node (ref "MCP73831") (pin "2") (pinfunction "VSS_2") (pintype "power_in"))
      (node (ref "R1_PWRUSB") (pin "1") (pinfunction "1_1") (pintype "passive"))
      (node (ref "R2") (pin "1") (pinfunction "1_1") (pintype "passive"))
      (node (ref "R2-USB1") (pin "2") (pinfunction "2_2") (pintype "passive"))
      (node (ref "R2-USB2") (pin "1") (pinfunction "1_1") (pintype "passive"))
      (node (ref "R2_BAT") (pin "1") (pinfunction "1_1") (pintype "passive"))
      (node (ref "R4") (pin "2") (pinfunction "2_2") (pintype "passive"))
      (node (ref "RESET_BUTTIN") (pin "1") (pinfunction "1_1") (pintype "passive"))
      (node (ref "RESET_BUTTIN") (pin "2") (pinfunction "2_2") (pintype "passive"))
      (node (ref "SENSOR2") (pin "1") (pinfunction "GND_1") (pintype "power_in"))
      (node (ref "SENSOR2") (pin "5") (pinfunction "SDO_5") (pintype "bidirectional"))
      (node (ref "SENSOR2") (pin "7") (pinfunction "GND_7") (pintype "power_in"))
      (node (ref "SJ1") (pin "1") (pinfunction "1_1") (pintype "passive"))
      (node (ref "TP4") (pin "TP") (pinfunction "TP_TP") (pintype "input"))
      (node (ref "TP5") (pin "TP") (pinfunction "TP_TP") (pintype "input"))
      (node (ref "U1") (pin "4") (pinfunction "GND_4") (pintype "power_in"))
      (node (ref "U1") (pin "9") (pinfunction "EXP_9") (pintype "passive"))
      (node (ref "U2") (pin "1") (pinfunction "GND_1") (pintype "power_in"))
      (node (ref "U2") (pin "28") (pinfunction "GND_28") (pintype "power_in"))
      (node (ref "U2") (pin "29_1") (pinfunction "GND_29_1") (pintype "power_in"))
      (node (ref "U2") (pin "29_2") (pinfunction "GND_29_2") (pintype "power_in"))
      (node (ref "U2") (pin "29_3") (pinfunction "GND_29_3") (pintype "power_in"))
      (node (ref "U2") (pin "29_4") (pinfunction "GND_29_4") (pintype "power_in"))
      (node (ref "U2") (pin "29_5") (pinfunction "GND_29_5") (pintype "power_in"))
      (node (ref "U2") (pin "29_6") (pinfunction "GND_29_6") (pintype "power_in"))
      (node (ref "U2") (pin "29_7") (pinfunction "GND_29_7") (pintype "power_in"))
      (node (ref "U2") (pin "29_8") (pinfunction "GND_29_8") (pintype "power_in"))
      (node (ref "U2") (pin "29_9") (pinfunction "GND_29_9") (pintype "power_in"))
      (node (ref "U3") (pin "13") (pinfunction "GND_13") (pintype "power_in"))
      (node (ref "U4") (pin "1") (pinfunction "CTG_1") (pintype "power_in"))
      (node (ref "U4") (pin "4") (pinfunction "GND_4") (pintype "power_in"))
      (node (ref "U4") (pin "6") (pinfunction "QSTRT_6") (pintype "input"))
      (node (ref "U4") (pin "9") (pinfunction "EP_9") (pintype "power_in"))
    )
    (net (code "14") (name "GPIO8") (class "Default")
      (node (ref "R1") (pin "2") (pinfunction "2_2") (pintype "passive"))
      (node (ref "U2") (pin "10") (pinfunction "IO8_10") (pintype "bidirectional"))
    )
    (net (code "15") (name "I2C_PW") (class "Default")
      (node (ref "C1") (pin "1") (pinfunction "1_1") (pintype "passive"))
      (node (ref "C2") (pin "1") (pinfunction "1_1") (pintype "passive"))
      (node (ref "R1-PINH") (pin "2") (pinfunction "2_2") (pintype "passive"))
      (node (ref "R2-PINH") (pin "2") (pinfunction "2_2") (pintype "passive"))
      (node (ref "SENSOR2") (pin "2") (pinfunction "CSB_2") (pintype "input"))
      (node (ref "SENSOR2") (pin "6") (pinfunction "VDDIO_6") (pintype "power_in"))
      (node (ref "SENSOR2") (pin "8") (pinfunction "VDD_8") (pintype "power_in"))
      (node (ref "U2") (pin "17") (pinfunction "IO19_17") (pintype "bidirectional"))
    )
    (net (code "16") (name "INT_RTC") (class "Default")
      (node (ref "R1-PINH1") (pin "1") (pinfunction "1_1") (pintype "passive"))
      (node (ref "TP15") (pin "TP") (pinfunction "TP_TP") (pintype "input"))
      (node (ref "U2") (pin "8") (pinfunction "IO0_8") (pintype "bidirectional"))
      (node (ref "U3") (pin "3") (pinfunction "SQW/~{INT}_3") (pintype "output"))
    )
    (net (code "17") (name "IO{slash}BOOT") (class "Default")
      (node (ref "BOOT_BUTTON") (pin "3") (pinfunction "3_3") (pintype "passive"))
      (node (ref "BOOT_BUTTON") (pin "4") (pinfunction "4_4") (pintype "passive"))
      (node (ref "C6") (pin "1") (pinfunction "1_1") (pintype "passive"))
      (node (ref "R_BOOT") (pin "2") (pinfunction "2_2") (pintype "passive"))
      (node (ref "U2") (pin "15") (pinfunction "IO9_15") (pintype "bidirectional"))
    )
    (net (code "18") (name "IO{slash}CHANGE") (class "Default")
      (node (ref "C10") (pin "1") (pinfunction "1_1") (pintype "passive"))
      (node (ref "CHANGE_BUTTON") (pin "3") (pinfunction "3_3") (pintype "passive"))
      (node (ref "CHANGE_BUTTON") (pin "4") (pinfunction "4_4") (pintype "passive"))
      (node (ref "R_CHANGE") (pin "2") (pinfunction "2_2") (pintype "passive"))
      (node (ref "U2") (pin "23") (pinfunction "IO15_23") (pintype "bidirectional"))
    )
    (net (code "19") (name "MISO") (class "Default")
      (node (ref "D12") (pin "1") (pinfunction "1_1") (pintype "passive"))
      (node (ref "J4") (pin "P7") (pinfunction "DAT0_P7") (pintype "bidirectional"))
      (node (ref "R8") (pin "1") (pinfunction "1_1") (pintype "passive"))
      (node (ref "TP6") (pin "TP") (pinfunction "TP_TP") (pintype "input"))
      (node (ref "U1") (pin "2") (pinfunction "DO(IO1)_2") (pintype "bidirectional"))
      (node (ref "U2") (pin "27") (pinfunction "IO2_27") (pintype "bidirectional"))
    )
    (net (code "20") (name "MOSI") (class "Default")
      (node (ref "D11") (pin "1") (pinfunction "1_1") (pintype "passive"))
      (node (ref "J1") (pin "14") (pinfunction "14_14") (pintype "bidirectional"))
      (node (ref "J4") (pin "P3") (pinfunction "CMD_P3") (pintype "bidirectional"))
      (node (ref "R7") (pin "1") (pinfunction "1_1") (pintype "passive"))
      (node (ref "TP7") (pin "TP") (pinfunction "TP_TP") (pintype "input"))
      (node (ref "U1") (pin "5") (pinfunction "DI(IO0)_5") (pintype "bidirectional"))
      (node (ref "U2") (pin "7") (pinfunction "IO7_7") (pintype "bidirectional"))
    )
    (net (code "21") (name "Net-(CHG_LED-PadC)") (class "Default")
      (node (ref "CHG_LED") (pin "C") (pinfunction "C_C") (pintype "passive"))
      (node (ref "R1_BAT") (pin "2") (pinfunction "2_2") (pintype "passive"))
    )
    (net (code "22") (name "Net-(D2-CATHODE)") (class "Default")
      (node (ref "C1_BAT1") (pin "1") (pinfunction "1_1") (pintype "passive"))
      (node (ref "D2") (pin "1") (pinfunction "CATHODE_1") (pintype "bidirectional"))
      (node (ref "IC1") (pin "1") (pinfunction "VIN_1") (pintype "bidirectional"))
      (node (ref "IC1") (pin "3") (pinfunction "CE_3") (pintype "bidirectional"))
      (node (ref "Q1") (pin "2") (pinfunction "S_2") (pintype "bidirectional"))
    )
    (net (code "23") (name "Net-(D3-A)") (class "Default")
      (node (ref "C4") (pin "1") (pinfunction "1_1") (pintype "passive"))
      (node (ref "D3") (pin "2") (pinfunction "A_2") (pintype "bidirectional"))
      (node (ref "D4") (pin "1") (pinfunction "K_1") (pintype "bidirectional"))
    )
    (net (code "24") (name "Net-(D7-CATHODE)") (class "Default")
      (node (ref "D7") (pin "1") (pinfunction "CATHODE_1") (pintype "bidirectional"))
      (node (ref "R_CAPACITOR") (pin "1") (pinfunction "1_1") (pintype "passive"))
    )
    (net (code "25") (name "Net-(EPD_C1-Pad1)") (class "Default")
      (node (ref "EPD_C1") (pin "1") (pinfunction "1_1") (pintype "passive"))
      (node (ref "J1") (pin "4") (pinfunction "4_4") (pintype "bidirectional"))
    )
    (net (code "26") (name "Net-(EPD_C2-Pad1)") (class "Default")
      (node (ref "EPD_C2") (pin "1") (pinfunction "1_1") (pintype "passive"))
      (node (ref "J1") (pin "5") (pinfunction "5_5") (pintype "bidirectional"))
    )
    (net (code "27") (name "Net-(EPD_C6-Pad1)") (class "Default")
      (node (ref "EPD_C6") (pin "1") (pinfunction "1_1") (pintype "passive"))
      (node (ref "J1") (pin "18") (pinfunction "18_18") (pintype "bidirectional"))
    )
    (net (code "28") (name "Net-(EPD_C7-Pad1)") (class "Default")
      (node (ref "EPD_C7") (pin "1") (pinfunction "1_1") (pintype "passive"))
      (node (ref "J1") (pin "19") (pinfunction "19_19") (pintype "bidirectional"))
    )
    (net (code "29") (name "Net-(EPD_C8-Pad1)") (class "Default")
      (node (ref "EPD_C8") (pin "1") (pinfunction "1_1") (pintype "passive"))
      (node (ref "J1") (pin "20") (pinfunction "20_20") (pintype "bidirectional"))
    )
    (net (code "30") (name "Net-(EPD_C10-Pad1)") (class "Default")
      (node (ref "EPD_C10") (pin "1") (pinfunction "1_1") (pintype "passive"))
      (node (ref "J1") (pin "22") (pinfunction "22_22") (pintype "bidirectional"))
    )
    (net (code "31") (name "Net-(EPD_C12-Pad1)") (class "Default")
      (node (ref "EPD_C12") (pin "1") (pinfunction "1_1") (pintype "passive"))
      (node (ref "J1") (pin "24") (pinfunction "24_24") (pintype "bidirectional"))
    )
    (net (code "32") (name "Net-(IC2-CT)") (class "Default")
      (node (ref "C_DELAY") (pin "1") (pinfunction "1_1") (pintype "passive"))
      (node (ref "IC2") (pin "5") (pinfunction "CT_5") (pintype "bidirectional"))
    )
    (net (code "33") (name "Net-(J2-PadA5)") (class "Default")
      (node (ref "J2") (pin "A5") (pinfunction "A5_A5") (pintype "bidirectional"))
      (node (ref "R2-USB1") (pin "1") (pinfunction "1_1") (pintype "passive"))
    )
    (net (code "34") (name "Net-(J2-PadB5)") (class "Default")
      (node (ref "J2") (pin "B5") (pinfunction "B5_B5") (pintype "bidirectional"))
      (node (ref "R2-USB2") (pin "2") (pinfunction "2_2") (pintype "passive"))
    )
    (net (code "35") (name "Net-(MCP73831-PROG)") (class "Default")
      (node (ref "MCP73831") (pin "5") (pinfunction "PROG_5") (pintype "input"))
      (node (ref "R2_BAT") (pin "2") (pinfunction "2_2") (pintype "passive"))
    )
    (net (code "36") (name "Net-(MCP73831-STAT)") (class "Default")
      (node (ref "MCP73831") (pin "1") (pinfunction "STAT_1") (pintype "output"))
      (node (ref "R1_BAT") (pin "1") (pinfunction "1_1") (pintype "passive"))
    )
    (net (code "37") (name "PREVGH") (class "Default")
      (node (ref "D5") (pin "1") (pinfunction "K_1") (pintype "bidirectional"))
      (node (ref "EPD_C9") (pin "1") (pinfunction "1_1") (pintype "passive"))
      (node (ref "J1") (pin "21") (pinfunction "21_21") (pintype "bidirectional"))
    )
    (net (code "38") (name "PREVGL") (class "Default")
      (node (ref "D4") (pin "2") (pinfunction "A_2") (pintype "bidirectional"))
      (node (ref "EPD_C11") (pin "1") (pinfunction "1_1") (pintype "passive"))
      (node (ref "J1") (pin "23") (pinfunction "23_23") (pintype "bidirectional"))
    )
    (net (code "39") (name "RESE") (class "Default")
      (node (ref "J1") (pin "3") (pinfunction "3_3") (pintype "bidirectional"))
      (node (ref "Q3") (pin "2") (pinfunction "S_2") (pintype "bidirectional"))
      (node (ref "R3") (pin "1") (pinfunction "1_1") (pintype "passive"))
    )
    (net (code "40") (name "RESE'") (class "Default")
      (node (ref "R2") (pin "2") (pinfunction "2_2") (pintype "passive"))
      (node (ref "R3") (pin "2") (pinfunction "2_2") (pintype "passive"))
      (node (ref "SJ1") (pin "2") (pinfunction "2_2") (pintype "passive"))
    )
    (net (code "41") (name "RESET") (class "Default")
      (node (ref "C5") (pin "1") (pinfunction "1_1") (pintype "passive"))
      (node (ref "IC2") (pin "1") (pinfunction "VOUT_1") (pintype "bidirectional"))
      (node (ref "RESET_BUTTIN") (pin "3") (pinfunction "3_3") (pintype "passive"))
      (node (ref "RESET_BUTTIN") (pin "4") (pinfunction "4_4") (pintype "passive"))
      (node (ref "R_RESET") (pin "2") (pinfunction "2_2") (pintype "passive"))
      (node (ref "U2") (pin "3") (pinfunction "EN_3") (pintype "input"))
    )
    (net (code "42") (name "RTC_RST") (class "Default")
      (node (ref "U2") (pin "16") (pinfunction "IO18_16") (pintype "bidirectional"))
      (node (ref "U3") (pin "4") (pinfunction "~{RST}_4") (pintype "input"))
    )
    (net (code "43") (name "RX") (class "Default")
      (node (ref "TP2") (pin "TP") (pinfunction "TP_TP") (pintype "input"))
      (node (ref "U2") (pin "24") (pinfunction "RXD0/GPIO17_24") (pintype "bidirectional"))
    )
    (net (code "44") (name "SCK") (class "Default")
      (node (ref "D10") (pin "1") (pinfunction "1_1") (pintype "passive"))
      (node (ref "J1") (pin "13") (pinfunction "13_13") (pintype "bidirectional"))
      (node (ref "J4") (pin "P5") (pinfunction "CLK_P5") (pintype "bidirectional"))
      (node (ref "R6") (pin "1") (pinfunction "1_1") (pintype "passive"))
      (node (ref "TP8") (pin "TP") (pinfunction "TP_TP") (pintype "input"))
      (node (ref "U1") (pin "6") (pinfunction "CLK_6") (pintype "input"))
      (node (ref "U2") (pin "6") (pinfunction "IO6_6") (pintype "bidirectional"))
    )
    (net (code "45") (name "SCL") (class "Default")
      (node (ref "J3") (pin "4") (pinfunction "4_4") (pintype "passive"))
      (node (ref "R2-PINH") (pin "1") (pinfunction "1_1") (pintype "passive"))
      (node (ref "SENSOR2") (pin "4") (pinfunction "SCK_4") (pintype "input"))
      (node (ref "U2") (pin "20") (pinfunction "IO22_20") (pintype "bidirectional"))
      (node (ref "U3") (pin "16") (pinfunction "SCL_16") (pintype "input"))
      (node (ref "U4") (pin "7") (pinfunction "SCL_7") (pintype "input"))
    )
    (net (code "46") (name "SDA") (class "Default")
      (node (ref "J3") (pin "3") (pinfunction "3_3") (pintype "passive"))
      (node (ref "R1-PINH") (pin "1") (pinfunction "1_1") (pintype "passive"))
      (node (ref "SENSOR2") (pin "3") (pinfunction "SDI_3") (pintype "bidirectional"))
      (node (ref "U2") (pin "19") (pinfunction "IO21_19") (pintype "bidirectional"))
      (node (ref "U3") (pin "15") (pinfunction "SDA_15") (pintype "bidirectional"))
      (node (ref "U4") (pin "8") (pinfunction "SDA_8") (pintype "bidirectional"))
    )
    (net (code "47") (name "SRC") (class "Default")
      (node (ref "C4") (pin "2") (pinfunction "2_2") (pintype "passive"))
      (node (ref "D5") (pin "2") (pinfunction "A_2") (pintype "bidirectional"))
      (node (ref "L1") (pin "1") (pinfunction "1_1") (pintype "passive"))
      (node (ref "Q3") (pin "3") (pinfunction "D_3") (pintype "bidirectional"))
    )
    (net (code "48") (name "SS_SD") (class "Default")
      (node (ref "D8") (pin "1") (pinfunction "1_1") (pintype "passive"))
      (node (ref "J4") (pin "P2") (pinfunction "CD/DAT3_P2") (pintype "bidirectional"))
      (node (ref "R10") (pin "1") (pinfunction "1_1") (pintype "passive"))
      (node (ref "U2") (pin "4") (pinfunction "IO4_4") (pintype "bidirectional"))
    )
    (net (code "49") (name "TX") (class "Default")
      (node (ref "TP1") (pin "TP") (pinfunction "TP_TP") (pintype "input"))
      (node (ref "U2") (pin "25") (pinfunction "TXD0/GPIO16_25") (pintype "bidirectional"))
    )
    (net (code "50") (name "USB_D+") (class "Default")
      (node (ref "D1") (pin "1") (pinfunction "I/O1_1_1") (pintype "bidirectional"))
      (node (ref "U2") (pin "14") (pinfunction "IO13_14") (pintype "bidirectional"))
    )
    (net (code "51") (name "USB_D-") (class "Default")
      (node (ref "D1") (pin "3") (pinfunction "I/O2_1_3") (pintype "bidirectional"))
      (node (ref "U2") (pin "13") (pinfunction "IO12_13") (pintype "bidirectional"))
    )
    (net (code "52") (name "VBAT") (class "Default")
      (node (ref "C2_BAT") (pin "1") (pinfunction "1_1") (pintype "passive"))
      (node (ref "MCP73831") (pin "3") (pinfunction "VBAT_3") (pintype "power_in"))
      (node (ref "Q1") (pin "3") (pinfunction "D_3") (pintype "bidirectional"))
      (node (ref "TP3") (pin "TP") (pinfunction "TP_TP") (pintype "input"))
      (node (ref "U4") (pin "2") (pinfunction "CELL_2") (pintype "power_in"))
      (node (ref "U4") (pin "3") (pinfunction "VDD_3") (pintype "power_in"))
    )
    (net (code "53") (name "VBUS") (class "Default")
      (node (ref "C1_BAT") (pin "1") (pinfunction "1_1") (pintype "passive"))
      (node (ref "C4_USB") (pin "2") (pinfunction "2_2") (pintype "passive"))
      (node (ref "C5_USB") (pin "2") (pinfunction "2_2") (pintype "passive"))
      (node (ref "CHG_LED") (pin "A") (pinfunction "A_A") (pintype "passive"))
      (node (ref "D1") (pin "5") (pinfunction "VBUS_5") (pintype "bidirectional"))
      (node (ref "D2") (pin "2") (pinfunction "ANODE_2") (pintype "bidirectional"))
      (node (ref "MCP73831") (pin "4") (pinfunction "VIN_4") (pintype "power_in"))
      (node (ref "PFMP.050.1") (pin "2") (pinfunction "2_2") (pintype "passive"))
      (node (ref "Q1") (pin "1") (pinfunction "G_1") (pintype "bidirectional"))
      (node (ref "R1_PWRUSB") (pin "2") (pinfunction "2_2") (pintype "passive"))
      (node (ref "TP14") (pin "TP") (pinfunction "TP_TP") (pintype "input"))
    )
    (net (code "54") (name "VRTC") (class "Default")
      (node (ref "C10_SUPERCAP") (pin "1") (pinfunction "1_1") (pintype "passive"))
      (node (ref "C8") (pin "1") (pinfunction "1_1") (pintype "passive"))
      (node (ref "R_CAPACITOR") (pin "2") (pinfunction "2_2") (pintype "passive"))
      (node (ref "U3") (pin "14") (pinfunction "VBAT_14") (pintype "power_in"))
    )
    (net (code "55") (name "VUSB") (class "Default")
      (node (ref "J2") (pin "A4") (pinfunction "A4_A4") (pintype "bidirectional"))
      (node (ref "J2") (pin "A9") (pinfunction "A9_A9") (pintype "bidirectional"))
      (node (ref "J2") (pin "B4") (pinfunction "B4_B4") (pintype "bidirectional"))
      (node (ref "J2") (pin "B9") (pinfunction "B9_B9") (pintype "bidirectional"))
      (node (ref "PFMP.050.1") (pin "1") (pinfunction "1_1") (pintype "passive"))
    )
    (net (code "56") (name "unconnected-(IC1-NC-Pad4)") (class "Default")
      (node (ref "IC1") (pin "4") (pinfunction "NC_4") (pintype "no_connect"))
    )
    (net (code "57") (name "unconnected-(IC2-NC-Pad4)") (class "Default")
      (node (ref "IC2") (pin "4") (pinfunction "NC_4") (pintype "no_connect"))
    )
    (net (code "58") (name "unconnected-(J1-Pad1)") (class "Default")
      (node (ref "J1") (pin "1") (pinfunction "1_1") (pintype "bidirectional"))
    )
    (net (code "59") (name "unconnected-(J1-Pad6)") (class "Default")
      (node (ref "J1") (pin "6") (pinfunction "6_6") (pintype "bidirectional"))
    )
    (net (code "60") (name "unconnected-(J1-Pad7)") (class "Default")
      (node (ref "J1") (pin "7") (pinfunction "7_7") (pintype "bidirectional"))
    )
    (net (code "61") (name "unconnected-(J2-PadA8)") (class "Default")
      (node (ref "J2") (pin "A8") (pinfunction "A8_A8") (pintype "bidirectional"))
    )
    (net (code "62") (name "unconnected-(J2-PadB8)") (class "Default")
      (node (ref "J2") (pin "B8") (pinfunction "B8_B8") (pintype "bidirectional"))
    )
    (net (code "63") (name "unconnected-(J4-DAT1-PadP8)") (class "Default")
      (node (ref "J4") (pin "P8") (pinfunction "DAT1_P8") (pintype "bidirectional"))
    )
    (net (code "64") (name "unconnected-(J4-DAT2-PadP1)") (class "Default")
      (node (ref "J4") (pin "P1") (pinfunction "DAT2_P1") (pintype "bidirectional"))
    )
    (net (code "65") (name "unconnected-(J4-DETECTION_1-PadS1)") (class "Default")
      (node (ref "J4") (pin "S1") (pinfunction "DETECTION_1_S1") (pintype "bidirectional"))
    )
    (net (code "66") (name "unconnected-(J4-DETECTION_2-PadS2)") (class "Default")
      (node (ref "J4") (pin "S2") (pinfunction "DETECTION_2_S2") (pintype "bidirectional"))
    )
    (net (code "67") (name "unconnected-(U2-NC-Pad22)") (class "Default")
      (node (ref "U2") (pin "22") (pinfunction "NC_22") (pintype "no_connect"))
    )
    (net (code "68") (name "unconnected-(U4-~{ALERT}-Pad5)") (class "Default")
      (node (ref "U4") (pin "5") (pinfunction "~{ALERT}_5") (pintype "output"))
    )
  )
)
